# ShinStrap_Interface.net
KiCad netlist of a schematic drawn in Altium Designer
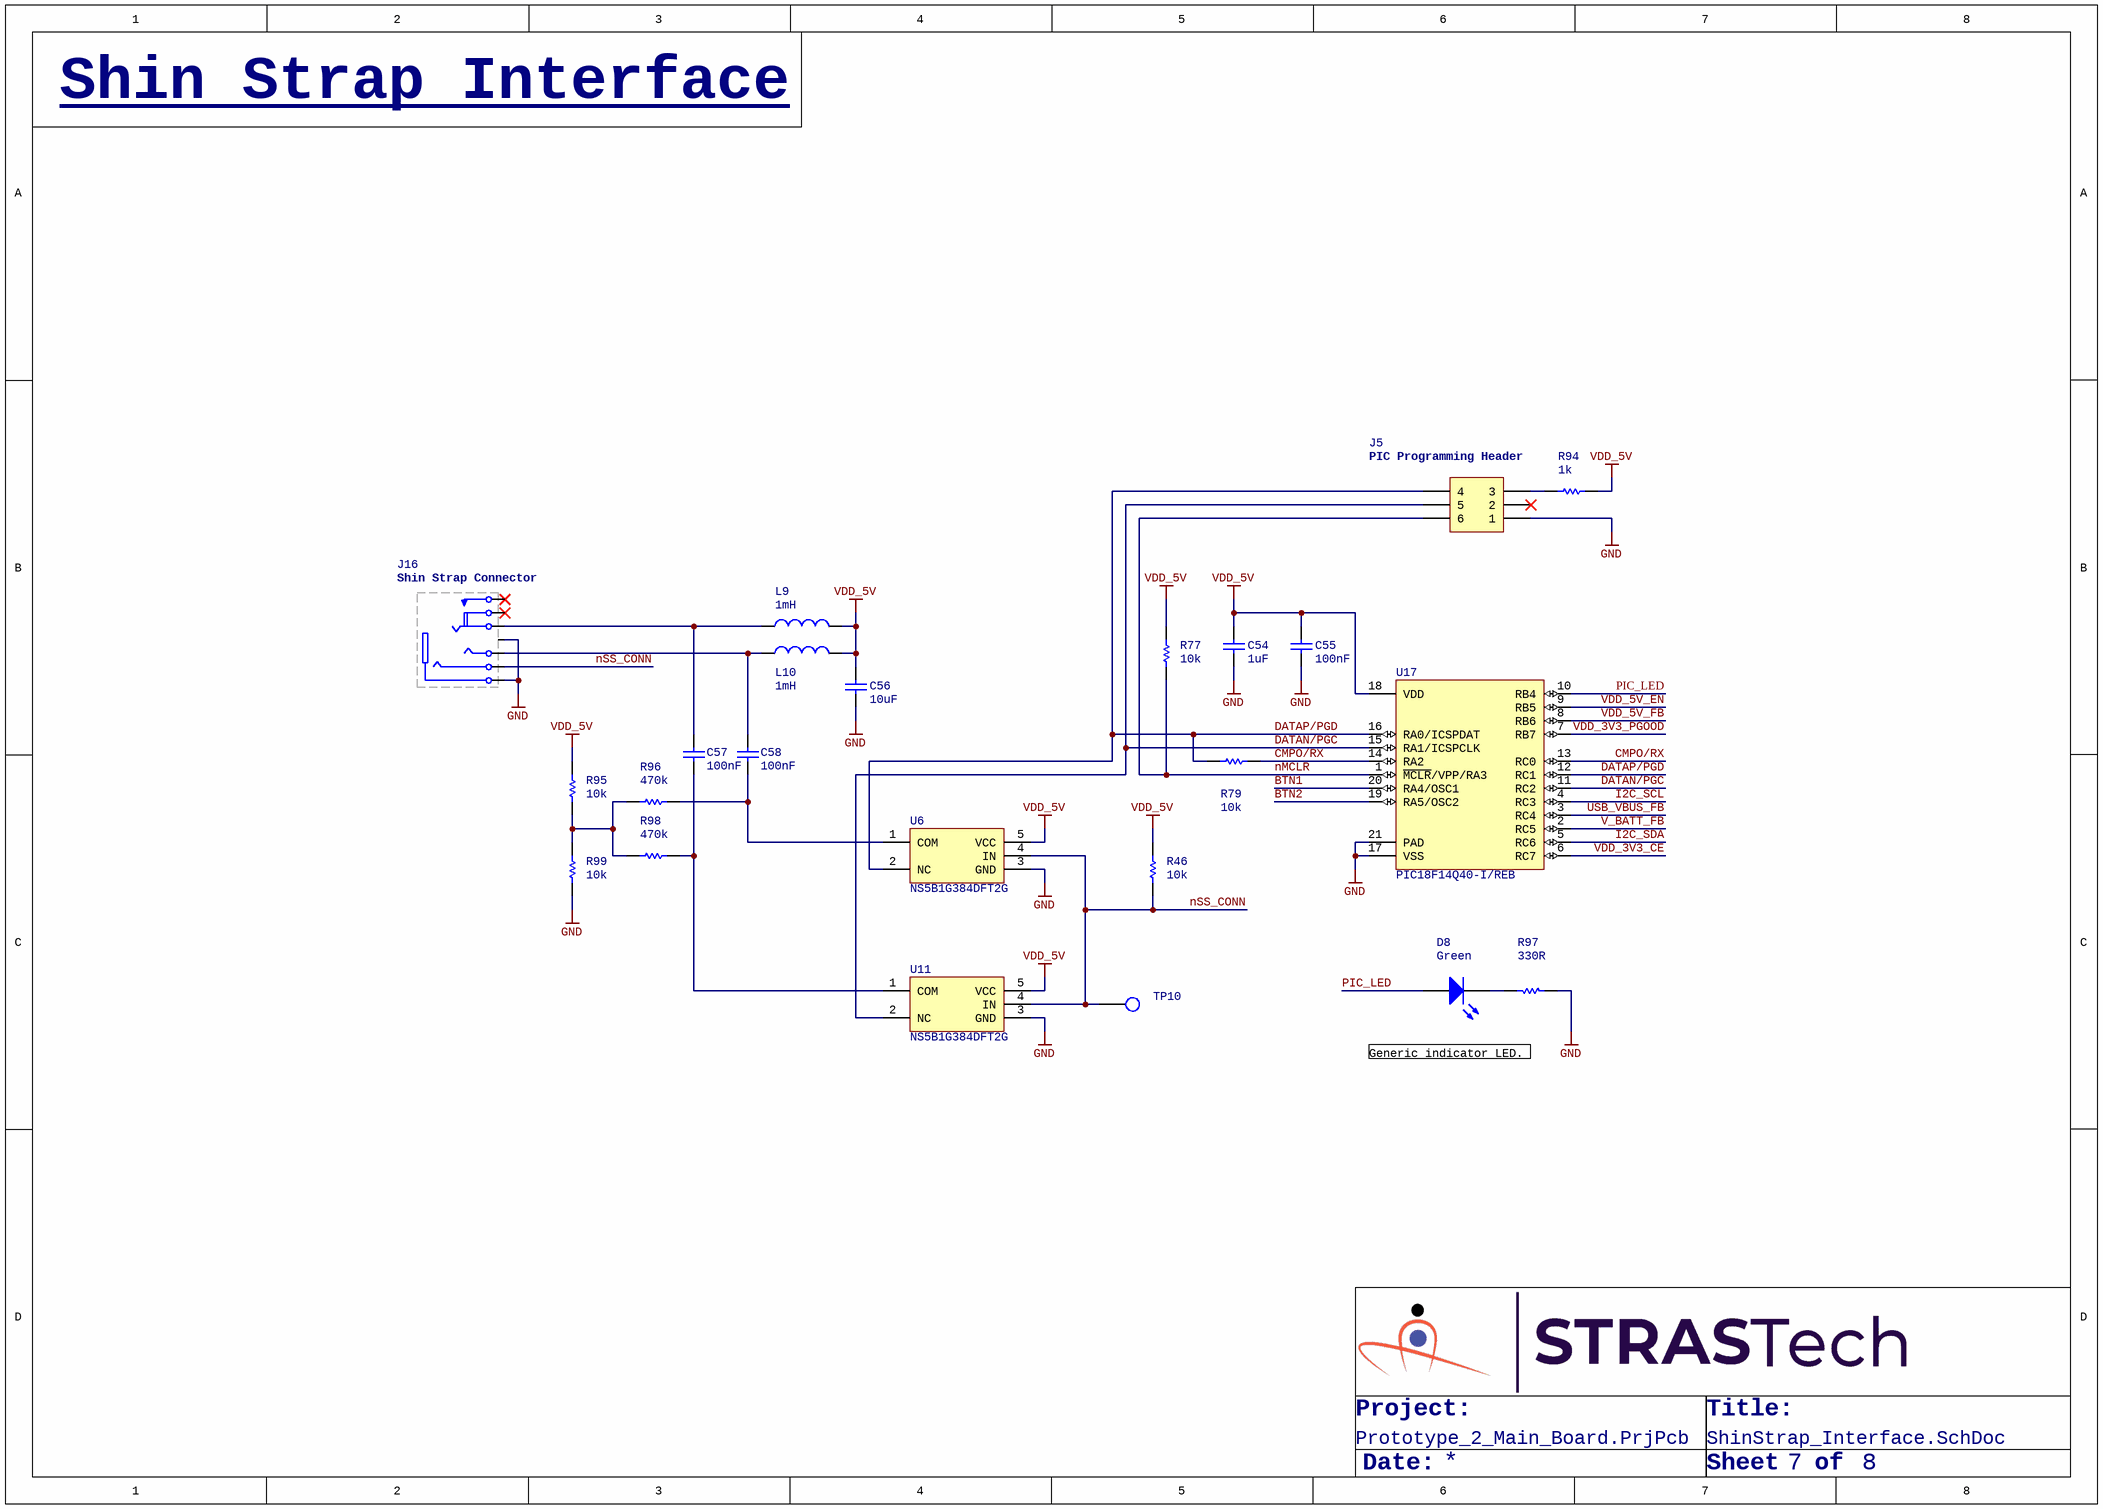
[diagram p0: ShinStrap_Interface.SchDoc]

(export (version "E")
  (design (tool "Eeschema 10.0.6"))
  (components
    (comp (ref "C54")
      (value "1uF")
      (footprint "Cap,SMD,0402")
      (description "1 µF ±10% 35V Ceramic Capacitor X5R 0402 (1005 Metric)")
      (fields
        (field (name "VENDOR PART NUMBER") "445-9073-1-ND")
        (field (name "MANUFACTURER") "TDK Corporation")
        (field (name "CREATEDBY") "Judd Foster")
      )
      (libsource (lib "symbols") (part "CAP,Cer,1uF,35VDC,X5R,0402"))
    )
    (comp (ref "C55")
      (value "100nF")
      (footprint "Cap,SMD,0402")
      (description "0.1µF ±10% 25V Ceramic Capacitor X7R 0402 (1005 Metric)")
      (fields
        (field (name "VENDOR PART NUMBER") "490-14603-1-ND")
        (field (name "MANUFACTURER") "Murata Electronics")
        (field (name "CREATEDBY") "Judd Foster")
      )
      (libsource (lib "symbols") (part "CAP,Cer,100nF,25VDC,X7R,0402"))
    )
    (comp (ref "C56")
      (value "10uF")
      (footprint "Cap,SMD,0402")
      (description "10 µF ±20% 10V Ceramic Capacitor X5R 0402 (1005 Metric)")
      (fields
        (field (name "VENDOR PART NUMBER") "1276-1450-1-ND")
        (field (name "MANUFACTURER") "Samsung Electro-Mechanics")
        (field (name "CREATEDBY") "Judd Foster")
      )
      (libsource (lib "symbols") (part "CAP,Cer,10uF,10VDC,X5R,0402"))
    )
    (comp (ref "C57")
      (value "100nF")
      (footprint "Cap,SMD,0402")
      (description "0.1µF ±10% 25V Ceramic Capacitor X7R 0402 (1005 Metric)")
      (fields
        (field (name "VENDOR PART NUMBER") "490-14603-1-ND")
        (field (name "MANUFACTURER") "Murata Electronics")
        (field (name "CREATEDBY") "Judd Foster")
      )
      (libsource (lib "symbols") (part "CAP,Cer,100nF,25VDC,X7R,0402"))
    )
    (comp (ref "C58")
      (value "100nF")
      (footprint "Cap,SMD,0402")
      (description "0.1µF ±10% 25V Ceramic Capacitor X7R 0402 (1005 Metric)")
      (fields
        (field (name "VENDOR PART NUMBER") "490-14603-1-ND")
        (field (name "MANUFACTURER") "Murata Electronics")
        (field (name "CREATEDBY") "Judd Foster")
      )
      (libsource (lib "symbols") (part "CAP,Cer,100nF,25VDC,X7R,0402"))
    )
    (comp (ref "D8")
      (value "Green")
      (footprint "LED,0603")
      (description "Green 530nm LED Indication - Discrete 3V 0603 (1608 Metric)")
      (fields
        (field (name "MANUFACTURER") "Stanley Electric Co")
        (field (name "MANUFACTURER PART NUMBER") "THG1111C-0005-TR")
        (field (name "CREATEDBY") "Judd Foster")
      )
      (libsource (lib "symbols") (part "LED,Green,SMD,0603"))
    )
    (comp (ref "J5")
      (value "Term,Header,3x2 Pin,1.27mm,SMD")
      (footprint "TERM,HEADER,3X2PIN,P1.27,SMD")
      (description "Connector Header Surface Mount 6 position 0.050\" (1.27mm)")
      (fields
        (field (name "VENDOR PART NUMBER") "609-3693-1-ND")
        (field (name "MANUFACTURER") "Amphenol ICC (FCI)")
        (field (name "CREATEDBY") "Judd Foster")
      )
      (libsource (lib "symbols") (part "Term,Header,3x2 Pin,1.27mm,SMD"))
    )
    (comp (ref "J16")
      (value "Conn,Jack,TRS,3.5mm,Thru,Shielded")
      (footprint "Conn,Jack,TRS,3.5mm,Thru,Shielded")
      (fields
        (field (name "MANUFACTURER") "CUI Devices")
        (field (name "MANUFACTURER PART NUMBER") "SJ-435107RS")
        (field (name "VENDOR PART NUMBER") "CP-435107RS-ND")
        (field (name "CREATEDBY") "Judd Foster")
      )
      (libsource (lib "symbols") (part "Conn,Jack,TRS,3.5mm,Thru,Shielded"))
    )
    (comp (ref "L9")
      (value "1mH")
      (footprint "IND,1210")
      (description "1 mH Unshielded Wirewound Inductor 100 mA 16.9Ohm Max 1210 (3225 Metric)")
      (fields
        (field (name "VENDOR PART NUMBER") "587-CBC3225T102MRCT-ND")
        (field (name "MANUFACTURER") "Taiyo Yuden")
        (field (name "CREATEDBY") "Judd Foster")
      )
      (libsource (lib "symbols") (part "IND,1mH,100mA,Wirewound,1210"))
    )
    (comp (ref "L10")
      (value "1mH")
      (footprint "IND,1210")
      (description "1 mH Unshielded Wirewound Inductor 100 mA 16.9Ohm Max 1210 (3225 Metric)")
      (fields
        (field (name "VENDOR PART NUMBER") "587-CBC3225T102MRCT-ND")
        (field (name "MANUFACTURER") "Taiyo Yuden")
        (field (name "CREATEDBY") "Judd Foster")
      )
      (libsource (lib "symbols") (part "IND,1mH,100mA,Wirewound,1210"))
    )
    (comp (ref "R46")
      (value "10k")
      (footprint "RES,0402")
      (description "10 kOhms ±5% 0.063W, 1/16W Chip Resistor 0402 (1005 Metric) Automotive AEC-Q200 Thick Film")
      (fields
        (field (name "VENDOR PART NUMBER") "RMCF0402JT10K0CT-ND")
        (field (name "MANUFACTURER") "Stackpole Electronics Inc")
        (field (name "CREATEDBY") "Judd Foster")
      )
      (libsource (lib "symbols") (part "RES,10k,5%,0.063W,0402"))
    )
    (comp (ref "R77")
      (value "10k")
      (footprint "RES,0402")
      (description "10 kOhms ±5% 0.063W, 1/16W Chip Resistor 0402 (1005 Metric) Automotive AEC-Q200 Thick Film")
      (fields
        (field (name "VENDOR PART NUMBER") "RMCF0402JT10K0CT-ND")
        (field (name "MANUFACTURER") "Stackpole Electronics Inc")
        (field (name "CREATEDBY") "Judd Foster")
      )
      (libsource (lib "symbols") (part "RES,10k,5%,0.063W,0402"))
    )
    (comp (ref "R79")
      (value "10k")
      (footprint "RES,0402")
      (description "10 kOhms ±5% 0.063W, 1/16W Chip Resistor 0402 (1005 Metric) Automotive AEC-Q200 Thick Film")
      (fields
        (field (name "VENDOR PART NUMBER") "RMCF0402JT10K0CT-ND")
        (field (name "MANUFACTURER") "Stackpole Electronics Inc")
        (field (name "CREATEDBY") "Judd Foster")
      )
      (libsource (lib "symbols") (part "RES,10k,5%,0.063W,0402"))
    )
    (comp (ref "R94")
      (value "1k")
      (footprint "RES,0402")
      (description "1 kOhms ±5% 0.063W, 1/16W Chip Resistor 0402 (1005 Metric) Automotive AEC-Q200 Thick Film")
      (fields
        (field (name "VENDOR PART NUMBER") "RMCF0402JT1K00CT-ND")
        (field (name "MANUFACTURER") "Stackpole Electronics Inc")
        (field (name "CREATEDBY") "Judd Foster")
      )
      (libsource (lib "symbols") (part "RES,1k,5%,0.063W,0402"))
    )
    (comp (ref "R95")
      (value "10k")
      (footprint "RES,0402")
      (description "10 kOhms ±5% 0.063W, 1/16W Chip Resistor 0402 (1005 Metric) Automotive AEC-Q200 Thick Film")
      (fields
        (field (name "VENDOR PART NUMBER") "RMCF0402JT10K0CT-ND")
        (field (name "MANUFACTURER") "Stackpole Electronics Inc")
        (field (name "CREATEDBY") "Judd Foster")
      )
      (libsource (lib "symbols") (part "RES,10k,5%,0.063W,0402"))
    )
    (comp (ref "R96")
      (value "470k")
      (footprint "RES,0402")
      (description "470 kOhms ±5% 0.063W, 1/16W Chip Resistor 0402 (1005 Metric) Automotive AEC-Q200 Thick Film")
      (fields
        (field (name "MANUFACTURER") "Stackpole Electronics Inc")
        (field (name "MANUFACTURER PART NUMBER") "RMCF0402JT470K")
        (field (name "CREATEDBY") "Judd Foster")
      )
      (libsource (lib "symbols") (part "RES,470k,5%,0.063W,0402"))
    )
    (comp (ref "R97")
      (value "330R")
      (footprint "RES,0402")
      (description "330 Ohms ±5% 0.063W, 1/16W Chip Resistor 0402 (1005 Metric) Automotive AEC-Q200 Thick Film")
      (fields
        (field (name "MANUFACTURER") "Stackpole Electronics Inc")
        (field (name "MANUFACTURER PART NUMBER") "RMCF0402JT330R")
        (field (name "CREATEDBY") "Judd Foster")
      )
      (libsource (lib "symbols") (part "RES,330R,5%,0.063W,0402"))
    )
    (comp (ref "R98")
      (value "470k")
      (footprint "RES,0402")
      (description "470 kOhms ±5% 0.063W, 1/16W Chip Resistor 0402 (1005 Metric) Automotive AEC-Q200 Thick Film")
      (fields
        (field (name "MANUFACTURER") "Stackpole Electronics Inc")
        (field (name "MANUFACTURER PART NUMBER") "RMCF0402JT470K")
        (field (name "CREATEDBY") "Judd Foster")
      )
      (libsource (lib "symbols") (part "RES,470k,5%,0.063W,0402"))
    )
    (comp (ref "R99")
      (value "10k")
      (footprint "RES,0402")
      (description "10 kOhms ±5% 0.063W, 1/16W Chip Resistor 0402 (1005 Metric) Automotive AEC-Q200 Thick Film")
      (fields
        (field (name "VENDOR PART NUMBER") "RMCF0402JT10K0CT-ND")
        (field (name "MANUFACTURER") "Stackpole Electronics Inc")
        (field (name "CREATEDBY") "Judd Foster")
      )
      (libsource (lib "symbols") (part "RES,10k,5%,0.063W,0402"))
    )
    (comp (ref "TP10")
      (value "TESTPOINT")
      (footprint "testpoint,smd,round,1mm")
      (description "PCB Testpoint")
      (fields (field (name "CREATEDBY") "Judd Foster"))
      (libsource (lib "symbols") (part "TESTPOINT"))
    )
    (comp (ref "U6")
      (value "NS5B1G384DFT2G")
      (footprint "SC70-5")
      (description "1 Circuit IC Switch 1:1 15Ohm SC-88A (SC-70-5/SOT-353)")
      (fields
        (field (name "MANUFACTURER") "onsemi")
        (field (name "VENDOR PART NUMBER") "NS5B1G384DFT2GOSCT-ND")
        (field (name "CREATEDBY") "Judd Foster")
      )
      (libsource (lib "symbols") (part "NS5B1G384DFT2G"))
    )
    (comp (ref "U11")
      (value "NS5B1G384DFT2G")
      (footprint "SC70-5")
      (description "1 Circuit IC Switch 1:1 15Ohm SC-88A (SC-70-5/SOT-353)")
      (fields
        (field (name "MANUFACTURER") "onsemi")
        (field (name "VENDOR PART NUMBER") "NS5B1G384DFT2GOSCT-ND")
        (field (name "CREATEDBY") "Judd Foster")
      )
      (libsource (lib "symbols") (part "NS5B1G384DFT2G"))
    )
    (comp (ref "U17")
      (value "PIC18F14Q40-I/REB")
      (footprint "IC,QFN-20,3x3,PAD,P0.4")
      (description "PIC series Microcontroller IC 8-Bit 64MHz 16KB (16K x 8) FLASH 20-VQFN (3x3)")
      (fields
        (field (name "MANUFACTURER") "Microchip Technology")
        (field (name "VENDOR PART NUMBER") "150-PIC18F14Q40-I/REB-ND")
        (field (name "CREATEDBY") "Judd Foster")
      )
      (libsource (lib "symbols") (part "PIC18F14Q40-I/REB"))
    )
  )
  (nets
    (net (code "1") (name "/BTN1") (class "Default")
      (node (ref "U17") (pin "20") (pinfunction "RA4/OSC1_20") (pintype "bidirectional"))
    )
    (net (code "2") (name "/BTN2") (class "Default")
      (node (ref "U17") (pin "19") (pinfunction "RA5/OSC2_19") (pintype "bidirectional"))
    )
    (net (code "3") (name "/CMPO{slash}RX") (class "Default")
      (node (ref "R79") (pin "1") (pinfunction "1_1") (pintype "passive"))
      (node (ref "U17") (pin "13") (pinfunction "RC0_13") (pintype "bidirectional"))
      (node (ref "U17") (pin "14") (pinfunction "RA2_14") (pintype "bidirectional"))
    )
    (net (code "4") (name "/DATAN{slash}PGC") (class "Default")
      (node (ref "J5") (pin "5") (pinfunction "5_5") (pintype "passive"))
      (node (ref "U11") (pin "2") (pinfunction "NC_2") (pintype "passive"))
      (node (ref "U17") (pin "11") (pinfunction "RC2_11") (pintype "bidirectional"))
      (node (ref "U17") (pin "15") (pinfunction "RA1/ICSPCLK_15") (pintype "bidirectional"))
    )
    (net (code "5") (name "/DATAP{slash}PGD") (class "Default")
      (node (ref "J5") (pin "4") (pinfunction "4_4") (pintype "passive"))
      (node (ref "R79") (pin "2") (pinfunction "2_2") (pintype "passive"))
      (node (ref "U17") (pin "12") (pinfunction "RC1_12") (pintype "bidirectional"))
      (node (ref "U17") (pin "16") (pinfunction "RA0/ICSPDAT_16") (pintype "bidirectional"))
      (node (ref "U6") (pin "2") (pinfunction "NC_2") (pintype "passive"))
    )
    (net (code "6") (name "/I2C_SCL") (class "Default")
      (node (ref "U17") (pin "4") (pinfunction "RC3_4") (pintype "bidirectional"))
    )
    (net (code "7") (name "/I2C_SDA") (class "Default")
      (node (ref "U17") (pin "5") (pinfunction "RC6_5") (pintype "bidirectional"))
    )
    (net (code "8") (name "/PIC_LED") (class "Default")
      (node (ref "D8") (pin "1") (pinfunction "A_1") (pintype "passive"))
      (node (ref "U17") (pin "10") (pinfunction "RB4_10") (pintype "bidirectional"))
    )
    (net (code "9") (name "/USB_VBUS_FB") (class "Default")
      (node (ref "U17") (pin "3") (pinfunction "RC4_3") (pintype "bidirectional"))
    )
    (net (code "10") (name "/VDD_3V3_CE") (class "Default")
      (node (ref "U17") (pin "6") (pinfunction "RC7_6") (pintype "bidirectional"))
    )
    (net (code "11") (name "/VDD_3V3_PGOOD") (class "Default")
      (node (ref "U17") (pin "7") (pinfunction "RB7_7") (pintype "bidirectional"))
    )
    (net (code "12") (name "/VDD_5V_EN") (class "Default")
      (node (ref "U17") (pin "9") (pinfunction "RB5_9") (pintype "bidirectional"))
    )
    (net (code "13") (name "/VDD_5V_FB") (class "Default")
      (node (ref "U17") (pin "8") (pinfunction "RB6_8") (pintype "bidirectional"))
    )
    (net (code "14") (name "/V_BATT_FB") (class "Default")
      (node (ref "U17") (pin "2") (pinfunction "RC5_2") (pintype "bidirectional"))
    )
    (net (code "15") (name "/nMCLR") (class "Default")
      (node (ref "J5") (pin "6") (pinfunction "6_6") (pintype "passive"))
      (node (ref "R77") (pin "1") (pinfunction "1_1") (pintype "passive"))
      (node (ref "U17") (pin "1") (pinfunction "~{MCLR}/VPP/RA3_1") (pintype "bidirectional"))
    )
    (net (code "16") (name "/nSS_CONN") (class "Default")
      (node (ref "J16") (pin "4") (pinfunction "R2_4") (pintype "passive"))
      (node (ref "R46") (pin "1") (pinfunction "1_1") (pintype "passive"))
      (node (ref "TP10") (pin "1") (pinfunction "TP_1") (pintype "passive"))
      (node (ref "U11") (pin "4") (pinfunction "IN_4") (pintype "passive"))
      (node (ref "U6") (pin "4") (pinfunction "IN_4") (pintype "passive"))
    )
    (net (code "17") (name "GND") (class "Default")
      (node (ref "C54") (pin "1") (pinfunction "1_1") (pintype "passive"))
      (node (ref "C55") (pin "1") (pinfunction "1_1") (pintype "passive"))
      (node (ref "C56") (pin "1") (pinfunction "1_1") (pintype "passive"))
      (node (ref "J16") (pin "0") (pinfunction "SH_0") (pintype "power_in"))
      (node (ref "J16") (pin "1") (pinfunction "S_1") (pintype "power_in"))
      (node (ref "J5") (pin "1") (pinfunction "1_1") (pintype "passive"))
      (node (ref "R97") (pin "1") (pinfunction "1_1") (pintype "passive"))
      (node (ref "R99") (pin "1") (pinfunction "1_1") (pintype "passive"))
      (node (ref "U11") (pin "3") (pinfunction "GND_3") (pintype "passive"))
      (node (ref "U17") (pin "17") (pinfunction "VSS_17") (pintype "power_in"))
      (node (ref "U17") (pin "21") (pinfunction "PAD_21") (pintype "passive"))
      (node (ref "U6") (pin "3") (pinfunction "GND_3") (pintype "passive"))
    )
    (net (code "18") (name "Net-(D8-K)") (class "Default")
      (node (ref "D8") (pin "2") (pinfunction "K_2") (pintype "passive"))
      (node (ref "R97") (pin "2") (pinfunction "2_2") (pintype "passive"))
    )
    (net (code "19") (name "Net-(J5-Pad3)") (class "Default")
      (node (ref "J5") (pin "3") (pinfunction "3_3") (pintype "passive"))
      (node (ref "R94") (pin "1") (pinfunction "1_1") (pintype "passive"))
    )
    (net (code "20") (name "Net-(J16-R1)") (class "Default")
      (node (ref "C57") (pin "2") (pinfunction "2_2") (pintype "passive"))
      (node (ref "J16") (pin "3") (pinfunction "R1_3") (pintype "passive"))
      (node (ref "L9") (pin "1") (pinfunction "1_1") (pintype "passive"))
    )
    (net (code "21") (name "Net-(J16-T)") (class "Default")
      (node (ref "C58") (pin "2") (pinfunction "2_2") (pintype "passive"))
      (node (ref "J16") (pin "2") (pinfunction "T_2") (pintype "passive"))
      (node (ref "L10") (pin "1") (pinfunction "1_1") (pintype "passive"))
    )
    (net (code "22") (name "Net-(R95-Pad1)") (class "Default")
      (node (ref "R95") (pin "1") (pinfunction "1_1") (pintype "passive"))
      (node (ref "R96") (pin "2") (pinfunction "2_2") (pintype "passive"))
      (node (ref "R98") (pin "2") (pinfunction "2_2") (pintype "passive"))
      (node (ref "R99") (pin "2") (pinfunction "2_2") (pintype "passive"))
    )
    (net (code "23") (name "Net-(U6-COM)") (class "Default")
      (node (ref "C58") (pin "1") (pinfunction "1_1") (pintype "passive"))
      (node (ref "R96") (pin "1") (pinfunction "1_1") (pintype "passive"))
      (node (ref "U6") (pin "1") (pinfunction "COM_1") (pintype "passive"))
    )
    (net (code "24") (name "Net-(U11-COM)") (class "Default")
      (node (ref "C57") (pin "1") (pinfunction "1_1") (pintype "passive"))
      (node (ref "R98") (pin "1") (pinfunction "1_1") (pintype "passive"))
      (node (ref "U11") (pin "1") (pinfunction "COM_1") (pintype "passive"))
    )
    (net (code "25") (name "VDD_5V") (class "Default")
      (node (ref "C54") (pin "2") (pinfunction "2_2") (pintype "passive"))
      (node (ref "C55") (pin "2") (pinfunction "2_2") (pintype "passive"))
      (node (ref "C56") (pin "2") (pinfunction "2_2") (pintype "passive"))
      (node (ref "L10") (pin "2") (pinfunction "2_2") (pintype "passive"))
      (node (ref "L9") (pin "2") (pinfunction "2_2") (pintype "passive"))
      (node (ref "R46") (pin "2") (pinfunction "2_2") (pintype "passive"))
      (node (ref "R77") (pin "2") (pinfunction "2_2") (pintype "passive"))
      (node (ref "R94") (pin "2") (pinfunction "2_2") (pintype "passive"))
      (node (ref "R95") (pin "2") (pinfunction "2_2") (pintype "passive"))
      (node (ref "U11") (pin "5") (pinfunction "VCC_5") (pintype "passive"))
      (node (ref "U17") (pin "18") (pinfunction "VDD_18") (pintype "power_in"))
      (node (ref "U6") (pin "5") (pinfunction "VCC_5") (pintype "passive"))
    )
    (net (code "26") (name "unconnected-(J5-Pad2)") (class "Default")
      (node (ref "J5") (pin "2") (pinfunction "2_2") (pintype "passive+no_connect"))
    )
    (net (code "27") (name "unconnected-(J16-IR1-Pad5)") (class "Default")
      (node (ref "J16") (pin "5") (pinfunction "IR1_5") (pintype "passive+no_connect"))
    )
    (net (code "28") (name "unconnected-(J16-R1S-Pad6)") (class "Default")
      (node (ref "J16") (pin "6") (pinfunction "R1S_6") (pintype "passive+no_connect"))
    )
  )
)
